# Calc_Schem.net
KiCad netlist of a schematic drawn in Altium Designer
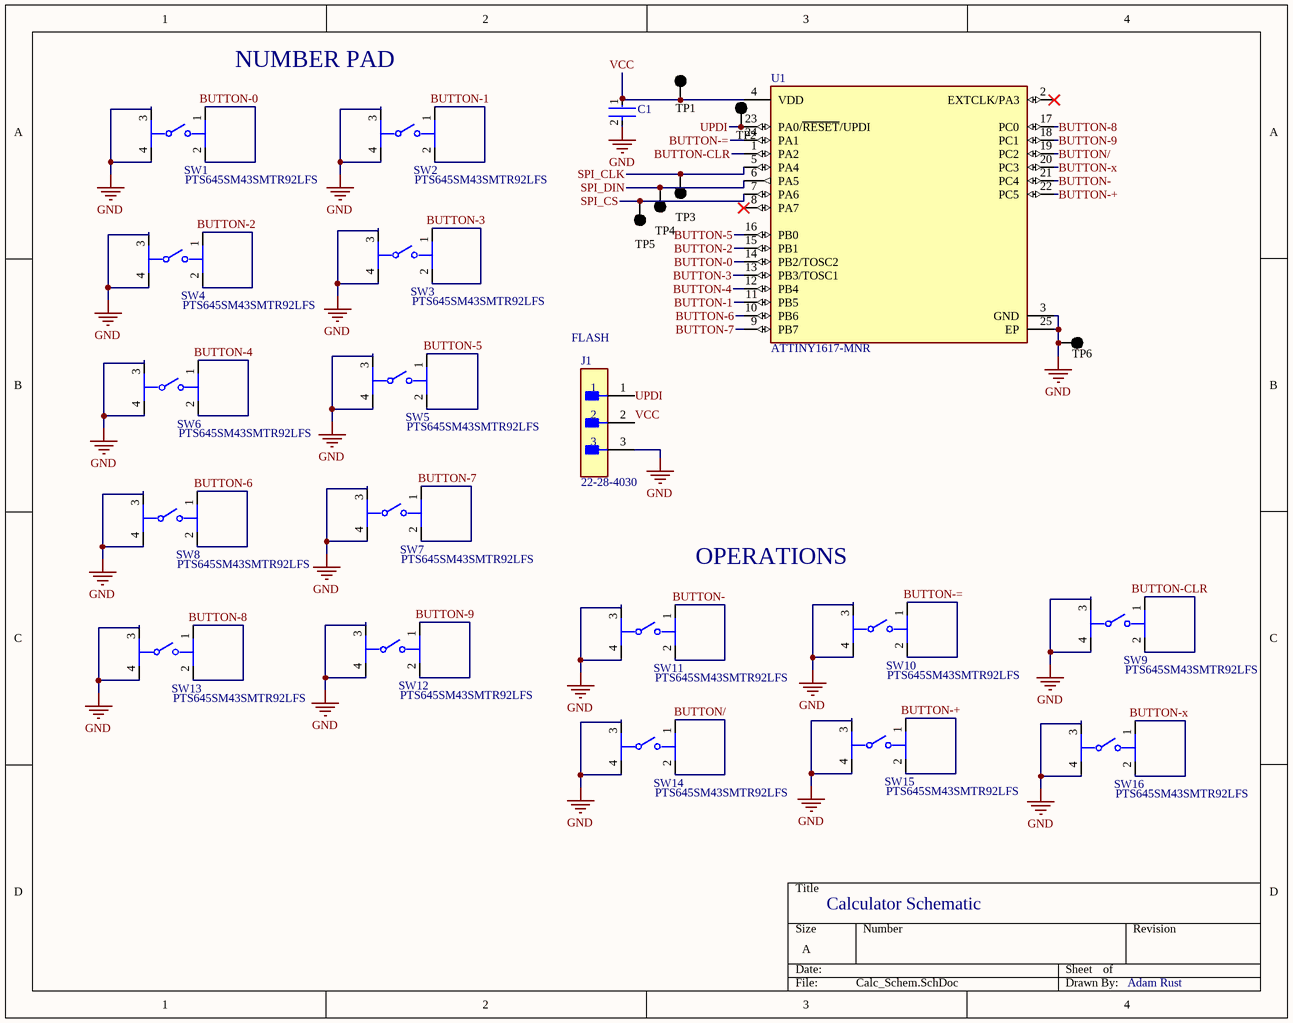
[diagram p0: Calc_Schem.SchDoc]

(export (version "E")
  (design (tool "Eeschema 10.0.6"))
  (components
    (comp (ref "C1")
      (value "GRM155R71C104KA88D")
      (footprint "FP-GRM15-MFG")
      (description "CAP CER 0.1UF 16V X7R 0402")
      (fields
        (field (name "TOLERANCE") "10%")
        (field (name "OCTOPART") "https://octopart.com/grm155r71c104ka88d-murata-196880")
      )
      (libsource (lib "Altium Content Vault") (part "236180d848d6139a670b325ea6854c9"))
    )
    (comp (ref "J1")
      (value "22-28-4030")
      (footprint "FP-22-28-4030-MFG")
      (description "UPDI PROG")
      (fields
        (field (name "OCTOPART") "https://octopart.com/0022284030-molex-10476094")
        (field (name "MANUFACTURER") "Molex")
      )
      (libsource (lib "Altium Content Vault") (part "0d3f023dd272f625e17a2be33dea85f"))
    )
    (comp (ref "SW1")
      (value "PTS645SM43SMTR92LFS")
      (footprint "FP-PTS645SM43SMTR92LFS-MFG")
      (description "SWITCH TACTILE SPST-NO 0.05A 12V")
      (libsource (lib "Altium Content Vault") (part "1adf0dd01260c80cf25a44bfd6b99ba"))
    )
    (comp (ref "SW2")
      (value "PTS645SM43SMTR92LFS")
      (footprint "FP-PTS645SM43SMTR92LFS-MFG")
      (description "SWITCH TACTILE SPST-NO 0.05A 12V")
      (libsource (lib "Altium Content Vault") (part "1adf0dd01260c80cf25a44bfd6b99ba"))
    )
    (comp (ref "SW3")
      (value "PTS645SM43SMTR92LFS")
      (footprint "FP-PTS645SM43SMTR92LFS-MFG")
      (description "SWITCH TACTILE SPST-NO 0.05A 12V")
      (libsource (lib "Altium Content Vault") (part "1adf0dd01260c80cf25a44bfd6b99ba"))
    )
    (comp (ref "SW4")
      (value "PTS645SM43SMTR92LFS")
      (footprint "FP-PTS645SM43SMTR92LFS-MFG")
      (description "SWITCH TACTILE SPST-NO 0.05A 12V")
      (libsource (lib "Altium Content Vault") (part "1adf0dd01260c80cf25a44bfd6b99ba"))
    )
    (comp (ref "SW5")
      (value "PTS645SM43SMTR92LFS")
      (footprint "FP-PTS645SM43SMTR92LFS-MFG")
      (description "SWITCH TACTILE SPST-NO 0.05A 12V")
      (libsource (lib "Altium Content Vault") (part "1adf0dd01260c80cf25a44bfd6b99ba"))
    )
    (comp (ref "SW6")
      (value "PTS645SM43SMTR92LFS")
      (footprint "FP-PTS645SM43SMTR92LFS-MFG")
      (description "SWITCH TACTILE SPST-NO 0.05A 12V")
      (libsource (lib "Altium Content Vault") (part "1adf0dd01260c80cf25a44bfd6b99ba"))
    )
    (comp (ref "SW7")
      (value "PTS645SM43SMTR92LFS")
      (footprint "FP-PTS645SM43SMTR92LFS-MFG")
      (description "SWITCH TACTILE SPST-NO 0.05A 12V")
      (libsource (lib "Altium Content Vault") (part "1adf0dd01260c80cf25a44bfd6b99ba"))
    )
    (comp (ref "SW8")
      (value "PTS645SM43SMTR92LFS")
      (footprint "FP-PTS645SM43SMTR92LFS-MFG")
      (description "SWITCH TACTILE SPST-NO 0.05A 12V")
      (libsource (lib "Altium Content Vault") (part "1adf0dd01260c80cf25a44bfd6b99ba"))
    )
    (comp (ref "SW9")
      (value "PTS645SM43SMTR92LFS")
      (footprint "FP-PTS645SM43SMTR92LFS-MFG")
      (description "SWITCH TACTILE SPST-NO 0.05A 12V")
      (libsource (lib "Altium Content Vault") (part "1adf0dd01260c80cf25a44bfd6b99ba"))
    )
    (comp (ref "SW10")
      (value "PTS645SM43SMTR92LFS")
      (footprint "FP-PTS645SM43SMTR92LFS-MFG")
      (description "SWITCH TACTILE SPST-NO 0.05A 12V")
      (libsource (lib "Altium Content Vault") (part "1adf0dd01260c80cf25a44bfd6b99ba"))
    )
    (comp (ref "SW11")
      (value "PTS645SM43SMTR92LFS")
      (footprint "FP-PTS645SM43SMTR92LFS-MFG")
      (description "SWITCH TACTILE SPST-NO 0.05A 12V")
      (libsource (lib "Altium Content Vault") (part "1adf0dd01260c80cf25a44bfd6b99ba"))
    )
    (comp (ref "SW12")
      (value "PTS645SM43SMTR92LFS")
      (footprint "FP-PTS645SM43SMTR92LFS-MFG")
      (description "SWITCH TACTILE SPST-NO 0.05A 12V")
      (libsource (lib "Altium Content Vault") (part "1adf0dd01260c80cf25a44bfd6b99ba"))
    )
    (comp (ref "SW13")
      (value "PTS645SM43SMTR92LFS")
      (footprint "FP-PTS645SM43SMTR92LFS-MFG")
      (description "SWITCH TACTILE SPST-NO 0.05A 12V")
      (libsource (lib "Altium Content Vault") (part "1adf0dd01260c80cf25a44bfd6b99ba"))
    )
    (comp (ref "SW14")
      (value "PTS645SM43SMTR92LFS")
      (footprint "FP-PTS645SM43SMTR92LFS-MFG")
      (description "SWITCH TACTILE SPST-NO 0.05A 12V")
      (libsource (lib "Altium Content Vault") (part "1adf0dd01260c80cf25a44bfd6b99ba"))
    )
    (comp (ref "SW15")
      (value "PTS645SM43SMTR92LFS")
      (footprint "FP-PTS645SM43SMTR92LFS-MFG")
      (description "SWITCH TACTILE SPST-NO 0.05A 12V")
      (libsource (lib "Altium Content Vault") (part "1adf0dd01260c80cf25a44bfd6b99ba"))
    )
    (comp (ref "SW16")
      (value "PTS645SM43SMTR92LFS")
      (footprint "FP-PTS645SM43SMTR92LFS-MFG")
      (description "SWITCH TACTILE SPST-NO 0.05A 12V")
      (libsource (lib "Altium Content Vault") (part "1adf0dd01260c80cf25a44bfd6b99ba"))
    )
    (comp (ref "TP1")
      (value "BTN")
      (footprint "KSTN-5011_V")
      (description "Test Point, Black, Through Hole, RoHS, Bulk")
      (fields (field (name "MANUFACTURER") "Keystone"))
      (libsource (lib "Altium Content Vault") (part "TESTPOINT_BLACK"))
    )
    (comp (ref "TP2")
      (value "BTN")
      (footprint "KSTN-5011_V")
      (description "Test Point, Black, Through Hole, RoHS, Bulk")
      (fields (field (name "MANUFACTURER") "Keystone"))
      (libsource (lib "Altium Content Vault") (part "TESTPOINT_BLACK"))
    )
    (comp (ref "TP3")
      (value "BTN")
      (footprint "KSTN-5011_V")
      (description "Test Point, Black, Through Hole, RoHS, Bulk")
      (fields (field (name "MANUFACTURER") "Keystone"))
      (libsource (lib "Altium Content Vault") (part "TESTPOINT_BLACK"))
    )
    (comp (ref "TP4")
      (value "BTN")
      (footprint "KSTN-5011_V")
      (description "Test Point, Black, Through Hole, RoHS, Bulk")
      (fields (field (name "MANUFACTURER") "Keystone"))
      (libsource (lib "Altium Content Vault") (part "TESTPOINT_BLACK"))
    )
    (comp (ref "TP5")
      (value "BTN")
      (footprint "KSTN-5011_V")
      (description "Test Point, Black, Through Hole, RoHS, Bulk")
      (fields (field (name "MANUFACTURER") "Keystone"))
      (libsource (lib "Altium Content Vault") (part "TESTPOINT_BLACK"))
    )
    (comp (ref "TP6")
      (value "BTN")
      (footprint "KSTN-5011_V")
      (description "Test Point, Black, Through Hole, RoHS, Bulk")
      (fields (field (name "MANUFACTURER") "Keystone"))
      (libsource (lib "Altium Content Vault") (part "TESTPOINT_BLACK"))
    )
    (comp (ref "U1")
      (value "ATTINY1617-MNR")
      (footprint "FP-C04-21386-IPC_A")
      (description "IC MCU 8BIT 16KB FLASH 24VQFN")
      (libsource (lib "Altium Content Vault") (part "3b8022cf9e231e6b75dc189be71ba34"))
    )
  )
  (nets
    (net (code "2") (name "/BUTTON-") (class "Default")
      (node (ref "SW11") (pin "1") (pinfunction "1_1") (pintype "passive"))
      (node (ref "SW11") (pin "2") (pinfunction "2_2") (pintype "passive"))
      (node (ref "U1") (pin "21") (pinfunction "PC4_21") (pintype "bidirectional"))
    )
    (net (code "3") (name "/BUTTON-+") (class "Default")
      (node (ref "SW15") (pin "1") (pinfunction "1_1") (pintype "passive"))
      (node (ref "SW15") (pin "2") (pinfunction "2_2") (pintype "passive"))
      (node (ref "U1") (pin "22") (pinfunction "PC5_22") (pintype "bidirectional"))
    )
    (net (code "4") (name "/BUTTON-0") (class "Default")
      (node (ref "SW1") (pin "1") (pinfunction "1_1") (pintype "passive"))
      (node (ref "SW1") (pin "2") (pinfunction "2_2") (pintype "passive"))
      (node (ref "U1") (pin "14") (pinfunction "PB2/TOSC2_14") (pintype "bidirectional"))
    )
    (net (code "5") (name "/BUTTON-1") (class "Default")
      (node (ref "SW2") (pin "1") (pinfunction "1_1") (pintype "passive"))
      (node (ref "SW2") (pin "2") (pinfunction "2_2") (pintype "passive"))
      (node (ref "U1") (pin "11") (pinfunction "PB5_11") (pintype "bidirectional"))
    )
    (net (code "6") (name "/BUTTON-2") (class "Default")
      (node (ref "SW4") (pin "1") (pinfunction "1_1") (pintype "passive"))
      (node (ref "SW4") (pin "2") (pinfunction "2_2") (pintype "passive"))
      (node (ref "U1") (pin "15") (pinfunction "PB1_15") (pintype "bidirectional"))
    )
    (net (code "7") (name "/BUTTON-3") (class "Default")
      (node (ref "SW3") (pin "1") (pinfunction "1_1") (pintype "passive"))
      (node (ref "SW3") (pin "2") (pinfunction "2_2") (pintype "passive"))
      (node (ref "U1") (pin "13") (pinfunction "PB3/TOSC1_13") (pintype "bidirectional"))
    )
    (net (code "8") (name "/BUTTON-4") (class "Default")
      (node (ref "SW6") (pin "1") (pinfunction "1_1") (pintype "passive"))
      (node (ref "SW6") (pin "2") (pinfunction "2_2") (pintype "passive"))
      (node (ref "U1") (pin "12") (pinfunction "PB4_12") (pintype "bidirectional"))
    )
    (net (code "9") (name "/BUTTON-5") (class "Default")
      (node (ref "SW5") (pin "1") (pinfunction "1_1") (pintype "passive"))
      (node (ref "SW5") (pin "2") (pinfunction "2_2") (pintype "passive"))
      (node (ref "U1") (pin "16") (pinfunction "PB0_16") (pintype "bidirectional"))
    )
    (net (code "10") (name "/BUTTON-6") (class "Default")
      (node (ref "SW8") (pin "1") (pinfunction "1_1") (pintype "passive"))
      (node (ref "SW8") (pin "2") (pinfunction "2_2") (pintype "passive"))
      (node (ref "U1") (pin "10") (pinfunction "PB6_10") (pintype "bidirectional"))
    )
    (net (code "11") (name "/BUTTON-7") (class "Default")
      (node (ref "SW7") (pin "1") (pinfunction "1_1") (pintype "passive"))
      (node (ref "SW7") (pin "2") (pinfunction "2_2") (pintype "passive"))
      (node (ref "U1") (pin "9") (pinfunction "PB7_9") (pintype "bidirectional"))
    )
    (net (code "12") (name "/BUTTON-8") (class "Default")
      (node (ref "SW13") (pin "1") (pinfunction "1_1") (pintype "passive"))
      (node (ref "SW13") (pin "2") (pinfunction "2_2") (pintype "passive"))
      (node (ref "U1") (pin "17") (pinfunction "PC0_17") (pintype "bidirectional"))
    )
    (net (code "13") (name "/BUTTON-9") (class "Default")
      (node (ref "SW12") (pin "1") (pinfunction "1_1") (pintype "passive"))
      (node (ref "SW12") (pin "2") (pinfunction "2_2") (pintype "passive"))
      (node (ref "U1") (pin "18") (pinfunction "PC1_18") (pintype "bidirectional"))
    )
    (net (code "14") (name "/BUTTON-=") (class "Default")
      (node (ref "SW10") (pin "1") (pinfunction "1_1") (pintype "passive"))
      (node (ref "SW10") (pin "2") (pinfunction "2_2") (pintype "passive"))
      (node (ref "U1") (pin "24") (pinfunction "PA1_24") (pintype "bidirectional"))
    )
    (net (code "15") (name "/BUTTON-CLR") (class "Default")
      (node (ref "SW9") (pin "1") (pinfunction "1_1") (pintype "passive"))
      (node (ref "SW9") (pin "2") (pinfunction "2_2") (pintype "passive"))
      (node (ref "U1") (pin "1") (pinfunction "PA2_1") (pintype "bidirectional"))
    )
    (net (code "16") (name "/BUTTON-x") (class "Default")
      (node (ref "SW16") (pin "1") (pinfunction "1_1") (pintype "passive"))
      (node (ref "SW16") (pin "2") (pinfunction "2_2") (pintype "passive"))
      (node (ref "U1") (pin "20") (pinfunction "PC3_20") (pintype "bidirectional"))
    )
    (net (code "17") (name "/BUTTON{slash}") (class "Default")
      (node (ref "SW14") (pin "1") (pinfunction "1_1") (pintype "passive"))
      (node (ref "SW14") (pin "2") (pinfunction "2_2") (pintype "passive"))
      (node (ref "U1") (pin "19") (pinfunction "PC2_19") (pintype "bidirectional"))
    )
    (net (code "18") (name "/SPI_CLK") (class "Default")
      (node (ref "TP3") (pin "1") (pinfunction "1_1") (pintype "passive"))
      (node (ref "U1") (pin "5") (pinfunction "PA4_5") (pintype "bidirectional"))
    )
    (net (code "19") (name "/SPI_CS") (class "Default")
      (node (ref "TP5") (pin "1") (pinfunction "1_1") (pintype "passive"))
      (node (ref "U1") (pin "7") (pinfunction "PA6_7") (pintype "bidirectional"))
    )
    (net (code "20") (name "/SPI_DIN") (class "Default")
      (node (ref "TP4") (pin "1") (pinfunction "1_1") (pintype "passive"))
      (node (ref "U1") (pin "6") (pinfunction "PA5_6") (pintype "output"))
    )
    (net (code "21") (name "/UPDI") (class "Default")
      (node (ref "J1") (pin "1") (pinfunction "1_1") (pintype "passive"))
      (node (ref "TP2") (pin "1") (pinfunction "1_1") (pintype "passive"))
      (node (ref "U1") (pin "23") (pinfunction "PA0/~{RESET}/UPDI_23") (pintype "bidirectional"))
    )
    (net (code "22") (name "/VCC") (class "Default")
      (node (ref "C1") (pin "1") (pinfunction "1_1") (pintype "passive"))
      (node (ref "J1") (pin "2") (pinfunction "2_2") (pintype "passive"))
      (node (ref "TP1") (pin "1") (pinfunction "1_1") (pintype "passive"))
      (node (ref "U1") (pin "4") (pinfunction "VDD_4") (pintype "power_in"))
    )
    (net (code "23") (name "GND") (class "Default")
      (node (ref "C1") (pin "2") (pinfunction "2_2") (pintype "passive"))
      (node (ref "J1") (pin "3") (pinfunction "3_3") (pintype "passive"))
      (node (ref "SW1") (pin "3") (pinfunction "3_3") (pintype "passive"))
      (node (ref "SW1") (pin "4") (pinfunction "4_4") (pintype "passive"))
      (node (ref "SW10") (pin "3") (pinfunction "3_3") (pintype "passive"))
      (node (ref "SW10") (pin "4") (pinfunction "4_4") (pintype "passive"))
      (node (ref "SW11") (pin "3") (pinfunction "3_3") (pintype "passive"))
      (node (ref "SW11") (pin "4") (pinfunction "4_4") (pintype "passive"))
      (node (ref "SW12") (pin "3") (pinfunction "3_3") (pintype "passive"))
      (node (ref "SW12") (pin "4") (pinfunction "4_4") (pintype "passive"))
      (node (ref "SW13") (pin "3") (pinfunction "3_3") (pintype "passive"))
      (node (ref "SW13") (pin "4") (pinfunction "4_4") (pintype "passive"))
      (node (ref "SW14") (pin "3") (pinfunction "3_3") (pintype "passive"))
      (node (ref "SW14") (pin "4") (pinfunction "4_4") (pintype "passive"))
      (node (ref "SW15") (pin "3") (pinfunction "3_3") (pintype "passive"))
      (node (ref "SW15") (pin "4") (pinfunction "4_4") (pintype "passive"))
      (node (ref "SW16") (pin "3") (pinfunction "3_3") (pintype "passive"))
      (node (ref "SW16") (pin "4") (pinfunction "4_4") (pintype "passive"))
      (node (ref "SW2") (pin "3") (pinfunction "3_3") (pintype "passive"))
      (node (ref "SW2") (pin "4") (pinfunction "4_4") (pintype "passive"))
      (node (ref "SW3") (pin "3") (pinfunction "3_3") (pintype "passive"))
      (node (ref "SW3") (pin "4") (pinfunction "4_4") (pintype "passive"))
      (node (ref "SW4") (pin "3") (pinfunction "3_3") (pintype "passive"))
      (node (ref "SW4") (pin "4") (pinfunction "4_4") (pintype "passive"))
      (node (ref "SW5") (pin "3") (pinfunction "3_3") (pintype "passive"))
      (node (ref "SW5") (pin "4") (pinfunction "4_4") (pintype "passive"))
      (node (ref "SW6") (pin "3") (pinfunction "3_3") (pintype "passive"))
      (node (ref "SW6") (pin "4") (pinfunction "4_4") (pintype "passive"))
      (node (ref "SW7") (pin "3") (pinfunction "3_3") (pintype "passive"))
      (node (ref "SW7") (pin "4") (pinfunction "4_4") (pintype "passive"))
      (node (ref "SW8") (pin "3") (pinfunction "3_3") (pintype "passive"))
      (node (ref "SW8") (pin "4") (pinfunction "4_4") (pintype "passive"))
      (node (ref "SW9") (pin "3") (pinfunction "3_3") (pintype "passive"))
      (node (ref "SW9") (pin "4") (pinfunction "4_4") (pintype "passive"))
      (node (ref "TP6") (pin "1") (pinfunction "1_1") (pintype "passive"))
      (node (ref "U1") (pin "25") (pinfunction "EP_25") (pintype "power_in"))
      (node (ref "U1") (pin "3") (pinfunction "GND_3") (pintype "power_in"))
    )
    (net (code "24") (name "unconnected-(U1-EXTCLK{slash}PA3-Pad2)") (class "Default")
      (node (ref "U1") (pin "2") (pinfunction "EXTCLK/PA3_2") (pintype "bidirectional+no_connect"))
    )
    (net (code "25") (name "unconnected-(U1-PA7-Pad8)") (class "Default")
      (node (ref "U1") (pin "8") (pinfunction "PA7_8") (pintype "bidirectional+no_connect"))
    )
  )
)
